# RS485_v1.net
KiCad netlist of a schematic drawn in EAGLE
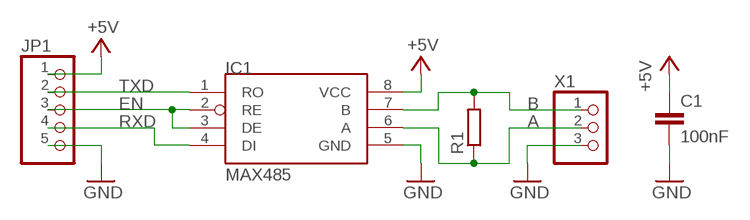
[diagram p0: schematic, sheet 1]

(export (version "E")
  (design (tool "Eeschema 10.0.6"))
  (components
    (comp (ref "C1")
      (value "100nF")
      (footprint "eagle-import:C0805K")
      (libsource (lib "eagle-import") (part "C-EUC0805K"))
    )
    (comp (ref "IC1")
      (value "MAX485")
      (footprint "eagle-import:SO08")
      (libsource (lib "eagle-import") (part "MAX485"))
    )
    (comp (ref "JP1")
      (value "PINHD-1X5")
      (footprint "eagle-import:1X05")
      (libsource (lib "eagle-import") (part "PINHD-1X5"))
    )
    (comp (ref "R1")
      (value "R-EU_R0805")
      (footprint "eagle-import:R0805")
      (libsource (lib "eagle-import") (part "R-EU_R0805"))
    )
    (comp (ref "X1")
      (value "W237-103")
      (footprint "eagle-import:W237-103")
      (libsource (lib "eagle-import") (part "W237-103"))
    )
  )
  (nets
    (net (code "1") (name "+5V") (class "Default")
      (node (ref "C1") (pin "1") (pinfunction "1_1") (pintype "passive"))
      (node (ref "IC1") (pin "8") (pinfunction "VCC_8") (pintype "bidirectional"))
      (node (ref "JP1") (pin "1") (pinfunction "1_1") (pintype "passive"))
    )
    (net (code "2") (name "/A") (class "Default")
      (node (ref "IC1") (pin "6") (pinfunction "A_6") (pintype "bidirectional"))
      (node (ref "R1") (pin "1") (pinfunction "1_1") (pintype "passive"))
      (node (ref "X1") (pin "2") (pinfunction "2_2") (pintype "passive"))
    )
    (net (code "3") (name "/B") (class "Default")
      (node (ref "IC1") (pin "7") (pinfunction "B_7") (pintype "bidirectional"))
      (node (ref "R1") (pin "2") (pinfunction "2_2") (pintype "passive"))
      (node (ref "X1") (pin "1") (pinfunction "1_1") (pintype "passive"))
    )
    (net (code "4") (name "/EN") (class "Default")
      (node (ref "IC1") (pin "2") (pinfunction "RE_2") (pintype "bidirectional"))
      (node (ref "IC1") (pin "3") (pinfunction "DE_3") (pintype "bidirectional"))
      (node (ref "JP1") (pin "3") (pinfunction "3_3") (pintype "passive"))
    )
    (net (code "5") (name "/RXD") (class "Default")
      (node (ref "IC1") (pin "4") (pinfunction "DI_4") (pintype "bidirectional"))
      (node (ref "JP1") (pin "4") (pinfunction "4_4") (pintype "passive"))
    )
    (net (code "6") (name "/TXD") (class "Default")
      (node (ref "IC1") (pin "1") (pinfunction "RO_1") (pintype "bidirectional"))
      (node (ref "JP1") (pin "2") (pinfunction "2_2") (pintype "passive"))
    )
    (net (code "7") (name "GND") (class "Default")
      (node (ref "C1") (pin "2") (pinfunction "2_2") (pintype "passive"))
      (node (ref "IC1") (pin "5") (pinfunction "GND_5") (pintype "bidirectional"))
      (node (ref "JP1") (pin "5") (pinfunction "5_5") (pintype "passive"))
      (node (ref "X1") (pin "3") (pinfunction "3_3") (pintype "passive"))
    )
  )
)
